# 001_01.net
KiCad netlist of a schematic drawn in EAGLE
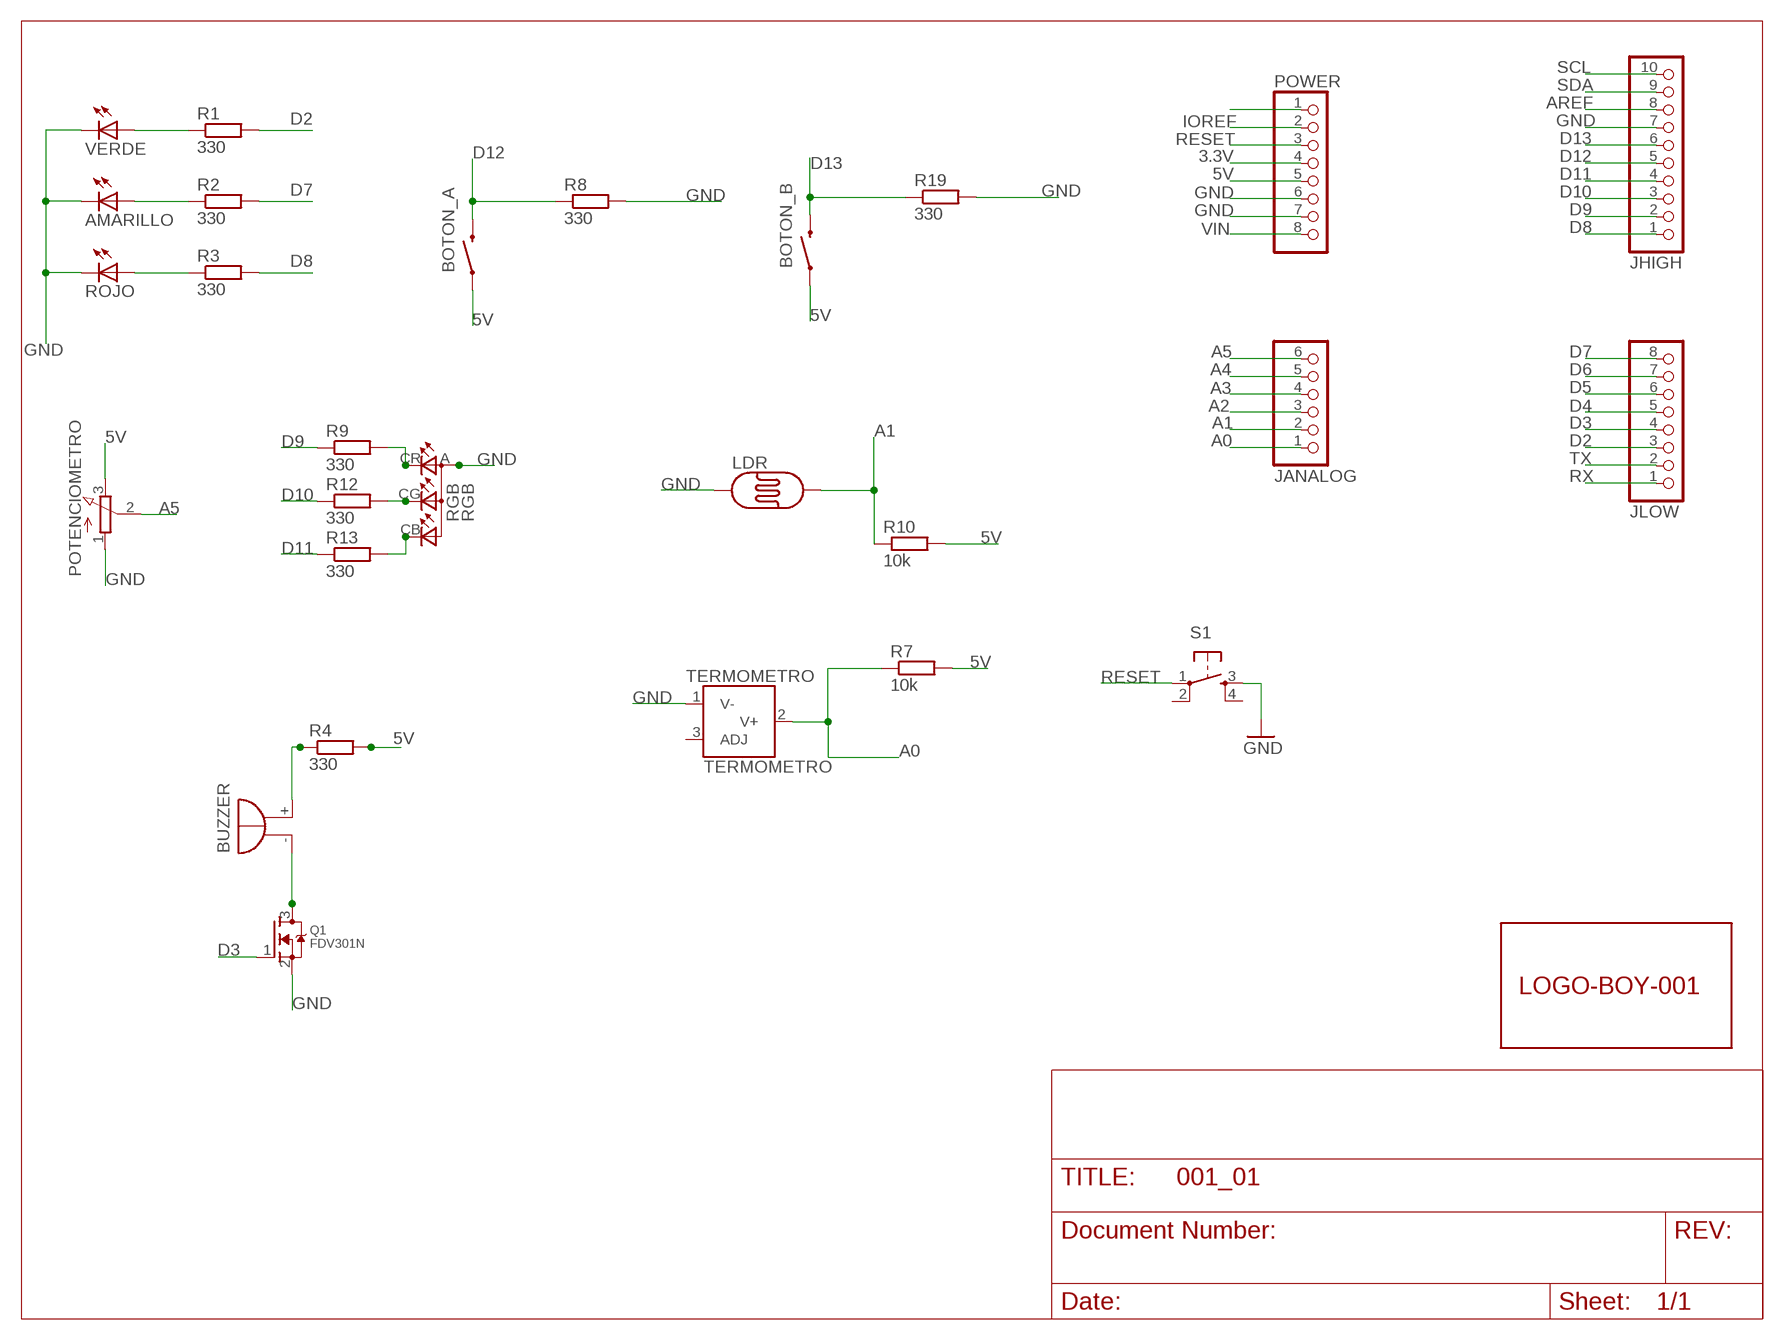
[diagram p0: schematic, sheet 1]

(export (version "E")
  (design (tool "Eeschema 10.0.6"))
  (components
    (comp (ref "AMARILLO")
      (value "LED10MM")
      (footprint "eagle-import:LED10MM")
      (libsource (lib "eagle-import") (part "LED10MM"))
    )
    (comp (ref "BOTON_A")
      (value "SWITCH-MOMENTARY-212MM")
      (footprint "eagle-import:TACTILE-PTH-12MM")
      (libsource (lib "eagle-import") (part "SWITCH-MOMENTARY-212MM"))
    )
    (comp (ref "BOTON_B")
      (value "SWITCH-MOMENTARY-212MM")
      (footprint "eagle-import:TACTILE-PTH-12MM")
      (libsource (lib "eagle-import") (part "SWITCH-MOMENTARY-212MM"))
    )
    (comp (ref "BUZZER")
      (value "BUZZER")
      (footprint "eagle-import:F_QMBIII")
      (libsource (lib "eagle-import") (part "F/QMBIII"))
    )
    (comp (ref "JANALOG")
      (value "6x1F-H8.5-L14.5mm")
      (footprint "eagle-import:1X06-TH")
      (libsource (lib "eagle-import") (part "PINHD-1X6TH"))
    )
    (comp (ref "JHIGH")
      (value "10x1F-H8.5-L14.5mm")
      (footprint "eagle-import:1X10-TH")
      (libsource (lib "eagle-import") (part "PINHD-1X10TH"))
    )
    (comp (ref "JLOW")
      (value "8x1F-H8.5-L14.5mm")
      (footprint "eagle-import:1X08-TH")
      (libsource (lib "eagle-import") (part "PINHD-1X8TH"))
    )
    (comp (ref "LDR")
      (value "FOTOCELDA")
      (footprint "eagle-import:PHOTOCELL")
      (libsource (lib "eagle-import") (part "PHOTOCELLPTH"))
    )
    (comp (ref "POTENCIOMETRO")
      (value "POTENCIOMETRO")
      (footprint "eagle-import:EVUF")
      (libsource (lib "eagle-import") (part "EVUAF3"))
    )
    (comp (ref "POWER")
      (value "8x1F-H8.5-L14.5mm")
      (footprint "eagle-import:1X08-TH")
      (libsource (lib "eagle-import") (part "PINHD-1X8TH"))
    )
    (comp (ref "Q1")
      (value "FDV301N")
      (footprint "eagle-import:SOT23-W")
      (libsource (lib "eagle-import") (part "MOSFET-NWAVE"))
    )
    (comp (ref "R1")
      (value "330")
      (footprint "eagle-import:M1206")
      (libsource (lib "eagle-import") (part "R-EU_M1206"))
    )
    (comp (ref "R2")
      (value "330")
      (footprint "eagle-import:M1206")
      (libsource (lib "eagle-import") (part "R-EU_M1206"))
    )
    (comp (ref "R3")
      (value "330")
      (footprint "eagle-import:M1206")
      (libsource (lib "eagle-import") (part "R-EU_M1206"))
    )
    (comp (ref "R4")
      (value "330")
      (footprint "eagle-import:M1206")
      (libsource (lib "eagle-import") (part "R-EU_M1206"))
    )
    (comp (ref "R7")
      (value "10k")
      (footprint "eagle-import:M1206")
      (libsource (lib "eagle-import") (part "R-EU_M1206"))
    )
    (comp (ref "R8")
      (value "330")
      (footprint "eagle-import:M1206")
      (libsource (lib "eagle-import") (part "R-EU_M1206"))
    )
    (comp (ref "R9")
      (value "330")
      (footprint "eagle-import:M1206")
      (libsource (lib "eagle-import") (part "R-EU_M1206"))
    )
    (comp (ref "R10")
      (value "10k")
      (footprint "eagle-import:M1206")
      (libsource (lib "eagle-import") (part "R-EU_M1206"))
    )
    (comp (ref "R12")
      (value "330")
      (footprint "eagle-import:M1206")
      (libsource (lib "eagle-import") (part "R-EU_M1206"))
    )
    (comp (ref "R13")
      (value "330")
      (footprint "eagle-import:M1206")
      (libsource (lib "eagle-import") (part "R-EU_M1206"))
    )
    (comp (ref "R19")
      (value "330")
      (footprint "eagle-import:M1206")
      (libsource (lib "eagle-import") (part "R-EU_M1206"))
    )
    (comp (ref "RGB")
      (value "RGB")
      (footprint "eagle-import:LED-RGB-10MM")
      (libsource (lib "eagle-import") (part "LED-RGB-10MM"))
    )
    (comp (ref "ROJO")
      (value "LED10MM")
      (footprint "eagle-import:LED10MM")
      (libsource (lib "eagle-import") (part "LED10MM"))
    )
    (comp (ref "S1")
      (value "TAC_SWITCHSMD")
      (footprint "eagle-import:TACTILE_SWITCH_SMD")
      (libsource (lib "eagle-import") (part "TAC_SWITCHSMD"))
    )
    (comp (ref "TERMOMETRO")
      (value "TERMOMETRO")
      (footprint "eagle-import:LM335Z")
      (libsource (lib "eagle-import") (part "LM335Z"))
    )
    (comp (ref "U$1")
      (value "LOGO-BOY-001")
      (footprint "eagle-import:LOGO-BOY-001")
      (libsource (lib "eagle-import") (part "LOGO-BOY-001"))
    )
    (comp (ref "VERDE")
      (value "LED10MM")
      (footprint "eagle-import:LED10MM")
      (libsource (lib "eagle-import") (part "LED10MM"))
    )
  )
  (nets
    (net (code "1") (name "/3.3V") (class "Default")
      (node (ref "POWER") (pin "4") (pinfunction "4_4") (pintype "passive"))
    )
    (net (code "2") (name "/5V") (class "Default")
      (node (ref "BOTON_A") (pin "1") (pinfunction "1_1") (pintype "passive"))
      (node (ref "BOTON_B") (pin "1") (pinfunction "1_1") (pintype "passive"))
      (node (ref "POTENCIOMETRO") (pin "3") (pinfunction "E_3") (pintype "passive"))
      (node (ref "POWER") (pin "5") (pinfunction "5_5") (pintype "passive"))
      (node (ref "R10") (pin "2") (pinfunction "2_2") (pintype "passive"))
      (node (ref "R4") (pin "2") (pinfunction "2_2") (pintype "passive"))
      (node (ref "R7") (pin "2") (pinfunction "2_2") (pintype "passive"))
    )
    (net (code "3") (name "/A0") (class "Default")
      (node (ref "JANALOG") (pin "1") (pinfunction "1_1") (pintype "passive"))
      (node (ref "R7") (pin "1") (pinfunction "1_1") (pintype "passive"))
      (node (ref "TERMOMETRO") (pin "2") (pinfunction "V+_2") (pintype "bidirectional"))
    )
    (net (code "4") (name "/A1") (class "Default")
      (node (ref "JANALOG") (pin "2") (pinfunction "2_2") (pintype "passive"))
      (node (ref "LDR") (pin "2") (pinfunction "P$2_2") (pintype "bidirectional"))
      (node (ref "R10") (pin "1") (pinfunction "1_1") (pintype "passive"))
    )
    (net (code "5") (name "/A2") (class "Default")
      (node (ref "JANALOG") (pin "3") (pinfunction "3_3") (pintype "passive"))
    )
    (net (code "6") (name "/A3") (class "Default")
      (node (ref "JANALOG") (pin "4") (pinfunction "4_4") (pintype "passive"))
    )
    (net (code "7") (name "/A4") (class "Default")
      (node (ref "JANALOG") (pin "5") (pinfunction "5_5") (pintype "passive"))
    )
    (net (code "8") (name "/A5") (class "Default")
      (node (ref "JANALOG") (pin "6") (pinfunction "6_6") (pintype "passive"))
      (node (ref "POTENCIOMETRO") (pin "2") (pinfunction "S_2") (pintype "passive"))
    )
    (net (code "9") (name "/AREF") (class "Default")
      (node (ref "JHIGH") (pin "8") (pinfunction "8_8") (pintype "passive"))
    )
    (net (code "10") (name "/D2") (class "Default")
      (node (ref "JLOW") (pin "3") (pinfunction "3_3") (pintype "passive"))
      (node (ref "R1") (pin "2") (pinfunction "2_2") (pintype "passive"))
    )
    (net (code "11") (name "/D3") (class "Default")
      (node (ref "JLOW") (pin "4") (pinfunction "4_4") (pintype "passive"))
      (node (ref "Q1") (pin "1") (pinfunction "G_1") (pintype "bidirectional"))
    )
    (net (code "12") (name "/D4") (class "Default")
      (node (ref "JLOW") (pin "5") (pinfunction "5_5") (pintype "passive"))
    )
    (net (code "13") (name "/D5") (class "Default")
      (node (ref "JLOW") (pin "6") (pinfunction "6_6") (pintype "passive"))
    )
    (net (code "14") (name "/D6") (class "Default")
      (node (ref "JLOW") (pin "7") (pinfunction "7_7") (pintype "passive"))
    )
    (net (code "15") (name "/D7") (class "Default")
      (node (ref "JLOW") (pin "8") (pinfunction "8_8") (pintype "passive"))
      (node (ref "R2") (pin "2") (pinfunction "2_2") (pintype "passive"))
    )
    (net (code "16") (name "/D8") (class "Default")
      (node (ref "JHIGH") (pin "1") (pinfunction "1_1") (pintype "passive"))
      (node (ref "R3") (pin "2") (pinfunction "2_2") (pintype "passive"))
    )
    (net (code "17") (name "/D9") (class "Default")
      (node (ref "JHIGH") (pin "2") (pinfunction "2_2") (pintype "passive"))
      (node (ref "R9") (pin "1") (pinfunction "1_1") (pintype "passive"))
    )
    (net (code "18") (name "/D10") (class "Default")
      (node (ref "JHIGH") (pin "3") (pinfunction "3_3") (pintype "passive"))
      (node (ref "R12") (pin "1") (pinfunction "1_1") (pintype "passive"))
    )
    (net (code "19") (name "/D11") (class "Default")
      (node (ref "JHIGH") (pin "4") (pinfunction "4_4") (pintype "passive"))
      (node (ref "R13") (pin "1") (pinfunction "1_1") (pintype "passive"))
    )
    (net (code "20") (name "/D12") (class "Default")
      (node (ref "BOTON_A") (pin "3") (pinfunction "2_3") (pintype "passive"))
      (node (ref "JHIGH") (pin "5") (pinfunction "5_5") (pintype "passive"))
      (node (ref "R8") (pin "1") (pinfunction "1_1") (pintype "passive"))
    )
    (net (code "21") (name "/D13") (class "Default")
      (node (ref "BOTON_B") (pin "3") (pinfunction "2_3") (pintype "passive"))
      (node (ref "JHIGH") (pin "6") (pinfunction "6_6") (pintype "passive"))
      (node (ref "R19") (pin "1") (pinfunction "1_1") (pintype "passive"))
    )
    (net (code "22") (name "/IOREF") (class "Default")
      (node (ref "POWER") (pin "2") (pinfunction "2_2") (pintype "passive"))
    )
    (net (code "23") (name "/RESET") (class "Default")
      (node (ref "POWER") (pin "3") (pinfunction "3_3") (pintype "passive"))
      (node (ref "S1") (pin "1") (pinfunction "1_1") (pintype "passive"))
    )
    (net (code "24") (name "/RX") (class "Default")
      (node (ref "JLOW") (pin "1") (pinfunction "1_1") (pintype "passive"))
    )
    (net (code "25") (name "/SCL") (class "Default")
      (node (ref "JHIGH") (pin "10") (pinfunction "10_10") (pintype "passive"))
    )
    (net (code "26") (name "/SDA") (class "Default")
      (node (ref "JHIGH") (pin "9") (pinfunction "9_9") (pintype "passive"))
    )
    (net (code "27") (name "/TX") (class "Default")
      (node (ref "JLOW") (pin "2") (pinfunction "2_2") (pintype "passive"))
    )
    (net (code "28") (name "/VIN") (class "Default")
      (node (ref "POWER") (pin "8") (pinfunction "8_8") (pintype "passive"))
    )
    (net (code "29") (name "GND") (class "Default")
      (node (ref "AMARILLO") (pin "K") (pinfunction "C_K") (pintype "passive"))
      (node (ref "JHIGH") (pin "7") (pinfunction "7_7") (pintype "passive"))
      (node (ref "LDR") (pin "1") (pinfunction "P$1_1") (pintype "bidirectional"))
      (node (ref "POTENCIOMETRO") (pin "1") (pinfunction "A_1") (pintype "passive"))
      (node (ref "POWER") (pin "6") (pinfunction "6_6") (pintype "passive"))
      (node (ref "POWER") (pin "7") (pinfunction "7_7") (pintype "passive"))
      (node (ref "Q1") (pin "2") (pinfunction "S_2") (pintype "bidirectional"))
      (node (ref "R19") (pin "2") (pinfunction "2_2") (pintype "passive"))
      (node (ref "R8") (pin "2") (pinfunction "2_2") (pintype "passive"))
      (node (ref "RGB") (pin "A") (pinfunction "A_A") (pintype "bidirectional"))
      (node (ref "ROJO") (pin "K") (pinfunction "C_K") (pintype "passive"))
      (node (ref "S1") (pin "3") (pinfunction "3_3") (pintype "passive"))
      (node (ref "TERMOMETRO") (pin "1") (pinfunction "V-_1") (pintype "bidirectional"))
      (node (ref "VERDE") (pin "K") (pinfunction "C_K") (pintype "passive"))
    )
    (net (code "30") (name "Net-(AMARILLO-PadA)") (class "Default")
      (node (ref "AMARILLO") (pin "A") (pinfunction "A_A") (pintype "passive"))
      (node (ref "R2") (pin "1") (pinfunction "1_1") (pintype "passive"))
    )
    (net (code "31") (name "Net-(BUZZER-+)") (class "Default")
      (node (ref "BUZZER") (pin "-") (pinfunction "+_-") (pintype "passive"))
      (node (ref "Q1") (pin "3") (pinfunction "D_3") (pintype "bidirectional"))
    )
    (net (code "32") (name "Net-(BUZZER--)") (class "Default")
      (node (ref "BUZZER") (pin "+") (pinfunction "-_+") (pintype "passive"))
      (node (ref "R4") (pin "1") (pinfunction "1_1") (pintype "passive"))
    )
    (net (code "33") (name "Net-(R1-Pad1)") (class "Default")
      (node (ref "R1") (pin "1") (pinfunction "1_1") (pintype "passive"))
      (node (ref "VERDE") (pin "A") (pinfunction "A_A") (pintype "passive"))
    )
    (net (code "34") (name "Net-(R3-Pad1)") (class "Default")
      (node (ref "R3") (pin "1") (pinfunction "1_1") (pintype "passive"))
      (node (ref "ROJO") (pin "A") (pinfunction "A_A") (pintype "passive"))
    )
    (net (code "35") (name "Net-(R9-Pad2)") (class "Default")
      (node (ref "R9") (pin "2") (pinfunction "2_2") (pintype "passive"))
      (node (ref "RGB") (pin "CR") (pinfunction "CR_CR") (pintype "bidirectional"))
    )
    (net (code "36") (name "Net-(R12-Pad2)") (class "Default")
      (node (ref "R12") (pin "2") (pinfunction "2_2") (pintype "passive"))
      (node (ref "RGB") (pin "CG") (pinfunction "CG_CG") (pintype "bidirectional"))
    )
    (net (code "37") (name "Net-(R13-Pad2)") (class "Default")
      (node (ref "R13") (pin "2") (pinfunction "2_2") (pintype "passive"))
      (node (ref "RGB") (pin "CB") (pinfunction "CB_CB") (pintype "bidirectional"))
    )
    (net (code "38") (name "unconnected-(POWER-Pad1)") (class "Default")
      (node (ref "POWER") (pin "1") (pinfunction "1_1") (pintype "passive"))
    )
    (net (code "39") (name "unconnected-(S1-Pad2)") (class "Default")
      (node (ref "S1") (pin "2") (pinfunction "2_2") (pintype "passive"))
    )
    (net (code "40") (name "unconnected-(S1-Pad4)") (class "Default")
      (node (ref "S1") (pin "4") (pinfunction "4_4") (pintype "passive"))
    )
    (net (code "41") (name "unconnected-(TERMOMETRO-ADJ-Pad3)") (class "Default")
      (node (ref "TERMOMETRO") (pin "3") (pinfunction "ADJ_3") (pintype "bidirectional"))
    )
  )
)
